# MungBeanSprout_Sch.net
KiCad netlist of a schematic drawn in Altium Designer
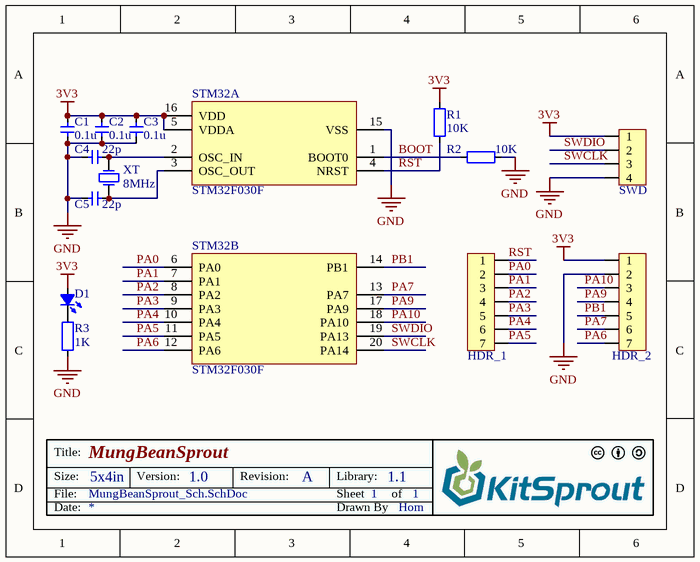
[diagram p0: MungBeanSprout_Sch.SchDoc]

(export (version "E")
  (design (tool "Eeschema 10.0.6"))
  (components
    (comp (ref "C1")
      (value "0.1u")
      (footprint "PCB_PassiveCap:CAP_0603")
      (description "Capacitor")
      (fields (field (name "Comment") "Cap_0603"))
      (libsource (lib "SCH_Passive") (part "Cap_0603"))
    )
    (comp (ref "C2")
      (value "0.1u")
      (footprint "PCB_PassiveCap:CAP_0603")
      (description "Capacitor")
      (fields (field (name "Comment") "Cap_0603"))
      (libsource (lib "SCH_Passive") (part "Cap_0603"))
    )
    (comp (ref "C3")
      (value "0.1u")
      (footprint "PCB_PassiveCap:CAP_0603")
      (description "Capacitor")
      (fields (field (name "Comment") "Cap_0603"))
      (libsource (lib "SCH_Passive") (part "Cap_0603"))
    )
    (comp (ref "C4")
      (value "22p")
      (footprint "PCB_PassiveCap:CAP_0603")
      (description "Capacitor")
      (fields (field (name "Comment") "Cap_0603"))
      (libsource (lib "SCH_Passive") (part "Cap_0603"))
    )
    (comp (ref "C5")
      (value "22p")
      (footprint "PCB_PassiveCap:CAP_0603")
      (description "Capacitor")
      (fields (field (name "Comment") "Cap_0603"))
      (libsource (lib "SCH_Passive") (part "Cap_0603"))
    )
    (comp (ref "D1")
      (value "LED_0603")
      (footprint "PCB_ActiveLED:LED_0603_BLUE")
      (description "LED")
      (libsource (lib "SCH_Active") (part "LED_0603"))
    )
    (comp (ref "HDR_1")
      (value "HDR1x7_2.54")
      (footprint "PCB_ConnectorHDR:HDR1X7_2.54_180")
      (description "Header")
      (libsource (lib "SCH_ConnectorHDR") (part "HDR1x7_2.54T"))
    )
    (comp (ref "HDR_2")
      (value "HDR1x7_2.54")
      (footprint "PCB_ConnectorHDR:HDR1X7_2.54_180")
      (description "Header")
      (libsource (lib "SCH_ConnectorHDR") (part "HDR1x7_2.54"))
    )
    (comp (ref "R1")
      (value "10K")
      (footprint "PCB_PassiveRes:RES_0603")
      (description "Resistor")
      (fields (field (name "Comment") "Res_0603"))
      (libsource (lib "SCH_Passive") (part "Res_0603"))
    )
    (comp (ref "R2")
      (value "10K")
      (footprint "PCB_PassiveRes:RES_0603")
      (description "Resistor")
      (fields (field (name "Comment") "Res_0603"))
      (libsource (lib "") (part "Res_0603_1"))
    )
    (comp (ref "R3")
      (value "1K")
      (footprint "PCB_PassiveRes:RES_0603")
      (description "Resistor")
      (fields (field (name "Comment") "Res_0603"))
      (libsource (lib "SCH_Passive") (part "Res_0603"))
    )
    (comp (ref "STM32")
      (value "STM32F030F")
      (footprint "PCB_IntegratedCircuit:TSSOP_E170_P0.65_20")
      (description "MCU")
      (libsource (lib "SCH_IntegratedCircuit") (part "STM32F030F"))
    )
    (comp (ref "SWD")
      (value "HDR1x4_2.54")
      (footprint "PCB_ConnectorHDR:HDR1X4_2.54_90F")
      (description "Header")
      (libsource (lib "SCH_ConnectorHDR") (part "HDR1x4_2.54"))
    )
    (comp (ref "XT")
      (value "8MHz")
      (footprint "PCB_Oscillator:XT_5032_2")
      (description "Crystal Oscillator")
      (fields (field (name "Comment") "XTAL_5032_2P"))
      (libsource (lib "SCH_Oscillator") (part "XTAL_5032_2P"))
    )
  )
  (nets
    (net (code "1") (name "/BOOT") (class "Default")
      (node (ref "R2") (pin "2") (pinfunction "2_2") (pintype "passive"))
      (node (ref "STM32") (pin "1") (pinfunction "BOOT0_1") (pintype "passive"))
    )
    (net (code "2") (name "/PA0") (class "Default")
      (node (ref "HDR_1") (pin "2") (pinfunction "2_2") (pintype "passive"))
      (node (ref "STM32") (pin "6") (pinfunction "PA0_6") (pintype "passive"))
    )
    (net (code "3") (name "/PA1") (class "Default")
      (node (ref "HDR_1") (pin "3") (pinfunction "3_3") (pintype "passive"))
      (node (ref "STM32") (pin "7") (pinfunction "PA1_7") (pintype "passive"))
    )
    (net (code "4") (name "/PA2") (class "Default")
      (node (ref "HDR_1") (pin "4") (pinfunction "4_4") (pintype "passive"))
      (node (ref "STM32") (pin "8") (pinfunction "PA2_8") (pintype "passive"))
    )
    (net (code "5") (name "/PA3") (class "Default")
      (node (ref "HDR_1") (pin "5") (pinfunction "5_5") (pintype "passive"))
      (node (ref "STM32") (pin "9") (pinfunction "PA3_9") (pintype "passive"))
    )
    (net (code "6") (name "/PA4") (class "Default")
      (node (ref "HDR_1") (pin "6") (pinfunction "6_6") (pintype "passive"))
      (node (ref "STM32") (pin "10") (pinfunction "PA4_10") (pintype "passive"))
    )
    (net (code "7") (name "/PA5") (class "Default")
      (node (ref "HDR_1") (pin "7") (pinfunction "7_7") (pintype "passive"))
      (node (ref "STM32") (pin "11") (pinfunction "PA5_11") (pintype "passive"))
    )
    (net (code "8") (name "/PA6") (class "Default")
      (node (ref "HDR_2") (pin "7") (pinfunction "7_7") (pintype "passive"))
      (node (ref "STM32") (pin "12") (pinfunction "PA6_12") (pintype "passive"))
    )
    (net (code "9") (name "/PA7") (class "Default")
      (node (ref "HDR_2") (pin "6") (pinfunction "6_6") (pintype "passive"))
      (node (ref "STM32") (pin "13") (pinfunction "PA7_13") (pintype "passive"))
    )
    (net (code "10") (name "/PA9") (class "Default")
      (node (ref "HDR_2") (pin "4") (pinfunction "4_4") (pintype "passive"))
      (node (ref "STM32") (pin "17") (pinfunction "PA9_17") (pintype "passive"))
    )
    (net (code "11") (name "/PA10") (class "Default")
      (node (ref "HDR_2") (pin "3") (pinfunction "3_3") (pintype "passive"))
      (node (ref "STM32") (pin "18") (pinfunction "PA10_18") (pintype "passive"))
    )
    (net (code "12") (name "/PB1") (class "Default")
      (node (ref "HDR_2") (pin "5") (pinfunction "5_5") (pintype "passive"))
      (node (ref "STM32") (pin "14") (pinfunction "PB1_14") (pintype "passive"))
    )
    (net (code "13") (name "/RST") (class "Default")
      (node (ref "HDR_1") (pin "1") (pinfunction "1_1") (pintype "passive"))
      (node (ref "R1") (pin "2") (pinfunction "2_2") (pintype "passive"))
      (node (ref "STM32") (pin "4") (pinfunction "NRST_4") (pintype "passive"))
    )
    (net (code "14") (name "/SWCLK") (class "Default")
      (node (ref "STM32") (pin "20") (pinfunction "PA14_20") (pintype "passive"))
      (node (ref "SWD") (pin "3") (pinfunction "3_3") (pintype "passive"))
    )
    (net (code "15") (name "/SWDIO") (class "Default")
      (node (ref "STM32") (pin "19") (pinfunction "PA13_19") (pintype "passive"))
      (node (ref "SWD") (pin "2") (pinfunction "2_2") (pintype "passive"))
    )
    (net (code "16") (name "3V3") (class "Default")
      (node (ref "C1") (pin "1") (pinfunction "1_1") (pintype "passive"))
      (node (ref "C2") (pin "1") (pinfunction "1_1") (pintype "passive"))
      (node (ref "C3") (pin "1") (pinfunction "1_1") (pintype "passive"))
      (node (ref "D1") (pin "1") (pinfunction "A_1") (pintype "passive"))
      (node (ref "HDR_2") (pin "1") (pinfunction "1_1") (pintype "passive"))
      (node (ref "R1") (pin "1") (pinfunction "1_1") (pintype "passive"))
      (node (ref "STM32") (pin "16") (pinfunction "VDD_16") (pintype "passive"))
      (node (ref "STM32") (pin "5") (pinfunction "VDDA_5") (pintype "passive"))
      (node (ref "SWD") (pin "1") (pinfunction "1_1") (pintype "passive"))
    )
    (net (code "17") (name "GND") (class "Default")
      (node (ref "C1") (pin "2") (pinfunction "2_2") (pintype "passive"))
      (node (ref "C2") (pin "2") (pinfunction "2_2") (pintype "passive"))
      (node (ref "C3") (pin "2") (pinfunction "2_2") (pintype "passive"))
      (node (ref "C4") (pin "1") (pinfunction "1_1") (pintype "passive"))
      (node (ref "C5") (pin "1") (pinfunction "1_1") (pintype "passive"))
      (node (ref "HDR_2") (pin "2") (pinfunction "2_2") (pintype "passive"))
      (node (ref "R2") (pin "1") (pinfunction "1_1") (pintype "passive"))
      (node (ref "R3") (pin "2") (pinfunction "2_2") (pintype "passive"))
      (node (ref "STM32") (pin "15") (pinfunction "VSS_15") (pintype "passive"))
      (node (ref "SWD") (pin "4") (pinfunction "4_4") (pintype "passive"))
    )
    (net (code "18") (name "Net-(D1-K)") (class "Default")
      (node (ref "D1") (pin "2") (pinfunction "K_2") (pintype "passive"))
      (node (ref "R3") (pin "1") (pinfunction "1_1") (pintype "passive"))
    )
    (net (code "19") (name "Net-(STM32A-OSC_IN)") (class "Default")
      (node (ref "C4") (pin "2") (pinfunction "2_2") (pintype "passive"))
      (node (ref "STM32") (pin "2") (pinfunction "OSC_IN_2") (pintype "passive"))
      (node (ref "XT") (pin "2") (pinfunction "OSC2_2") (pintype "passive"))
    )
    (net (code "20") (name "Net-(STM32A-OSC_OUT)") (class "Default")
      (node (ref "C5") (pin "2") (pinfunction "2_2") (pintype "passive"))
      (node (ref "STM32") (pin "3") (pinfunction "OSC_OUT_3") (pintype "passive"))
      (node (ref "XT") (pin "1") (pinfunction "OSC1_1") (pintype "passive"))
    )
  )
)
